# MINI_SAM_D51_r020_b002_Seeed.net
KiCad netlist of a schematic drawn in EAGLE
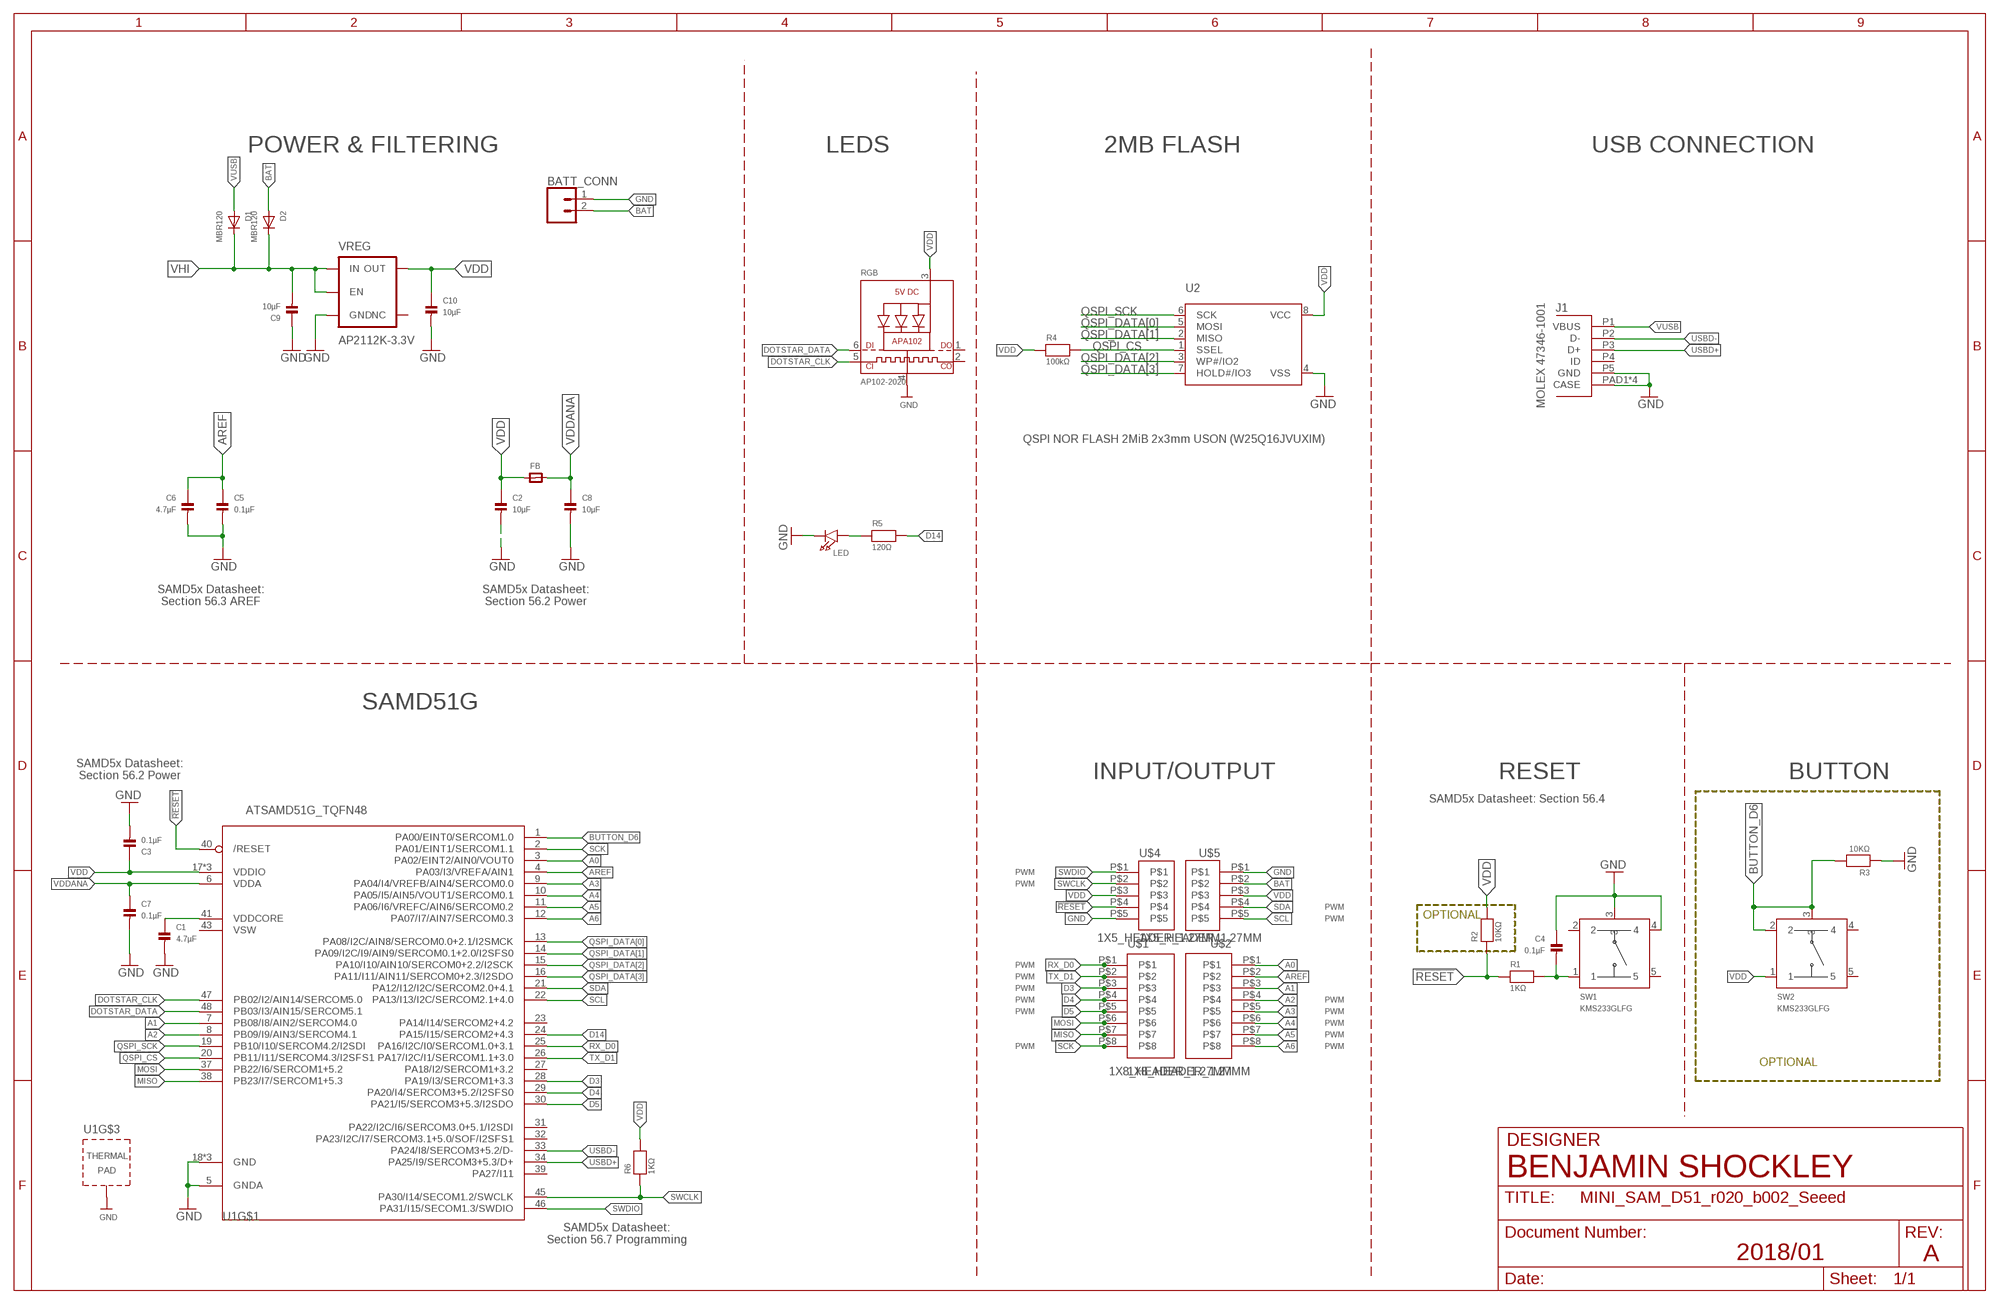
[diagram p0: schematic, sheet 1]

(export (version "E")
  (design (tool "Eeschema 10.0.6"))
  (components
    (comp (ref "BATT_CONN")
      (value "CONN_02-JST-2MM-SMT")
      (footprint "eagle-import:JST-2-SMD")
      (libsource (lib "eagle-import") (part "CONN_02-JST-2MM-SMT"))
    )
    (comp (ref "C1")
      (value "4.7µF")
      (footprint "eagle-import:_0603MP")
      (libsource (lib "eagle-import") (part "CAP_CERAMIC_0603MP"))
    )
    (comp (ref "C2")
      (value "10µF")
      (footprint "eagle-import:_0603MP")
      (libsource (lib "eagle-import") (part "CAP_CERAMIC_0603MP"))
    )
    (comp (ref "C3")
      (value "0.1µF")
      (footprint "eagle-import:_0603MP")
      (libsource (lib "eagle-import") (part "CAP_CERAMIC_0603MP"))
    )
    (comp (ref "C4")
      (value "0.1µF")
      (footprint "eagle-import:_0603MP")
      (libsource (lib "eagle-import") (part "CAP_CERAMIC_0603MP"))
    )
    (comp (ref "C5")
      (value "0.1µF")
      (footprint "eagle-import:_0603MP")
      (libsource (lib "eagle-import") (part "CAP_CERAMIC_0603MP"))
    )
    (comp (ref "C6")
      (value "4.7µF")
      (footprint "eagle-import:_0603MP")
      (libsource (lib "eagle-import") (part "CAP_CERAMIC_0603MP"))
    )
    (comp (ref "C7")
      (value "0.1µF")
      (footprint "eagle-import:_0603MP")
      (libsource (lib "eagle-import") (part "CAP_CERAMIC_0603MP"))
    )
    (comp (ref "C8")
      (value "10µF")
      (footprint "eagle-import:_0603MP")
      (libsource (lib "eagle-import") (part "CAP_CERAMIC_0603MP"))
    )
    (comp (ref "C9")
      (value "10µF")
      (footprint "eagle-import:_0603MP")
      (libsource (lib "eagle-import") (part "CAP_CERAMIC_0603MP"))
    )
    (comp (ref "C10")
      (value "10µF")
      (footprint "eagle-import:_0603MP")
      (libsource (lib "eagle-import") (part "CAP_CERAMIC_0603MP"))
    )
    (comp (ref "D1")
      (value "MBR120")
      (footprint "eagle-import:SOD-123FL")
      (libsource (lib "eagle-import") (part "DIODE_SOD-123FL"))
    )
    (comp (ref "D2")
      (value "MBR120")
      (footprint "eagle-import:SOD-123FL")
      (libsource (lib "eagle-import") (part "DIODE_SOD-123FL"))
    )
    (comp (ref "FB")
      (value "Impedence: 50 ohm @ 20 MHz, 220 Ohm @ 100 MHz; low DC resistance")
      (footprint "eagle-import:_0603MP")
      (libsource (lib "eagle-import") (part "FERRITE_0603MP"))
    )
    (comp (ref "J1")
      (value "MOLEX_47346-100147346")
      (footprint "eagle-import:MOLEX_47346-1001")
      (libsource (lib "eagle-import") (part "MOLEX_47346-100147346"))
    )
    (comp (ref "LED")
      (value "VLRK31Q1R2-GS08")
      (footprint "eagle-import:REVERSE_MOUNT_LED")
      (libsource (lib "eagle-import") (part "REVERSEMOUNTLED"))
    )
    (comp (ref "R1")
      (value "1KΩ")
      (footprint "eagle-import:_0603MP")
      (libsource (lib "eagle-import") (part "RESISTOR_0603MP"))
    )
    (comp (ref "R2")
      (value "10KΩ")
      (footprint "eagle-import:_0603MP")
      (libsource (lib "eagle-import") (part "RESISTOR_0603MP"))
    )
    (comp (ref "R3")
      (value "10KΩ")
      (footprint "eagle-import:_0603MP")
      (libsource (lib "eagle-import") (part "RESISTOR_0603MP"))
    )
    (comp (ref "R4")
      (value "100kΩ")
      (footprint "eagle-import:_0603MP")
      (libsource (lib "eagle-import") (part "RESISTOR_0603MP"))
    )
    (comp (ref "R5")
      (value "120Ω")
      (footprint "eagle-import:_0603MP")
      (libsource (lib "eagle-import") (part "RESISTOR_0603MP"))
    )
    (comp (ref "R6")
      (value "1KΩ")
      (footprint "eagle-import:_0603MP")
      (libsource (lib "eagle-import") (part "RESISTOR_0603MP"))
    )
    (comp (ref "RGB")
      (value "AP102-2020")
      (footprint "eagle-import:APA102_2020")
      (libsource (lib "eagle-import") (part "APA1022020"))
    )
    (comp (ref "SW1")
      (value "KMS233GLFG")
      (footprint "eagle-import:KMS_SWITCH")
      (libsource (lib "eagle-import") (part "KMS_SWITCHKMS"))
    )
    (comp (ref "SW2")
      (value "KMS233GLFG")
      (footprint "eagle-import:KMS_SWITCH")
      (libsource (lib "eagle-import") (part "KMS_SWITCHKMS"))
    )
    (comp (ref "U$1")
      (value "1X8_HEADER_1.27MM")
      (footprint "eagle-import:1X8_HEADER_1.27MM")
      (libsource (lib "eagle-import") (part "1X8_HEADER_1.27MM"))
    )
    (comp (ref "U$2")
      (value "1X8_HEADER_1.27MM")
      (footprint "eagle-import:1X8_HEADER_1.27MM")
      (libsource (lib "eagle-import") (part "1X8_HEADER_1.27MM"))
    )
    (comp (ref "U$4")
      (value "1X5_HEADER_1.27MM")
      (footprint "eagle-import:1X5_HEADER_1.27MM")
      (libsource (lib "eagle-import") (part "1X5_HEADER_1.27MM"))
    )
    (comp (ref "U$5")
      (value "1X5_HEADER_1.27MM")
      (footprint "eagle-import:1X5_HEADER_1.27MM")
      (libsource (lib "eagle-import") (part "1X5_HEADER_1.27MM"))
    )
    (comp (ref "U1")
      (value "ATSAMD51G_TQFN48")
      (footprint "eagle-import:TQFN48_7MM")
      (libsource (lib "eagle-import") (part "ATSAMD51G_TQFN48"))
    )
    (comp (ref "U2")
      (value "QSPI NOR FLASH 2MiB 2x3mm USON (W25Q16JVUXIM)")
      (footprint "eagle-import:USON8")
      (libsource (lib "eagle-import") (part "SPIFLASH_8PINUX"))
    )
    (comp (ref "VREG")
      (value "AP2112K-3.3V")
      (footprint "eagle-import:SOT23-5")
      (libsource (lib "eagle-import") (part "V_REG_AP2112K-3.3V"))
    )
  )
  (nets
    (net (code "1") (name "/VSW") (class "Default")
      (node (ref "U1") (pin "43") (pinfunction "VSW_43") (pintype "power_in"))
    )
    (net (code "2") (name "/~{RESET}") (class "Default")
      (node (ref "R1") (pin "1") (pinfunction "1_1") (pintype "passive"))
      (node (ref "R2") (pin "1") (pinfunction "1_1") (pintype "passive"))
      (node (ref "U$4") (pin "P$4") (pinfunction "P$4_P$4") (pintype "bidirectional"))
      (node (ref "U1") (pin "40") (pinfunction "/RESET_40") (pintype "bidirectional"))
    )
    (net (code "3") (name "A0") (class "Default")
      (node (ref "U$2") (pin "P$1") (pinfunction "P$1_P$1") (pintype "bidirectional"))
      (node (ref "U1") (pin "3") (pinfunction "PA02/EINT2/AIN0/VOUT0_3") (pintype "bidirectional"))
    )
    (net (code "4") (name "A1") (class "Default")
      (node (ref "U$2") (pin "P$3") (pinfunction "P$3_P$3") (pintype "bidirectional"))
      (node (ref "U1") (pin "7") (pinfunction "PB08/I8/AIN2/SERCOM4.0_7") (pintype "bidirectional"))
    )
    (net (code "5") (name "A2") (class "Default")
      (node (ref "U$2") (pin "P$4") (pinfunction "P$4_P$4") (pintype "bidirectional"))
      (node (ref "U1") (pin "8") (pinfunction "PB09/I9/AIN3/SERCOM4.1_8") (pintype "bidirectional"))
    )
    (net (code "6") (name "A3") (class "Default")
      (node (ref "U$2") (pin "P$5") (pinfunction "P$5_P$5") (pintype "bidirectional"))
      (node (ref "U1") (pin "9") (pinfunction "PA04/I4/VREFB/AIN4/SERCOM0.0_9") (pintype "bidirectional"))
    )
    (net (code "7") (name "A4") (class "Default")
      (node (ref "U$2") (pin "P$6") (pinfunction "P$6_P$6") (pintype "bidirectional"))
      (node (ref "U1") (pin "10") (pinfunction "PA05/I5/AIN5/VOUT1/SERCOM0.1_10") (pintype "bidirectional"))
    )
    (net (code "8") (name "A5") (class "Default")
      (node (ref "U$2") (pin "P$7") (pinfunction "P$7_P$7") (pintype "bidirectional"))
      (node (ref "U1") (pin "11") (pinfunction "PA06/I6/VREFC/AIN6/SERCOM0.2_11") (pintype "bidirectional"))
    )
    (net (code "9") (name "A6") (class "Default")
      (node (ref "U$2") (pin "P$8") (pinfunction "P$8_P$8") (pintype "bidirectional"))
      (node (ref "U1") (pin "12") (pinfunction "PA07/I7/AIN7/SERCOM0.3_12") (pintype "bidirectional"))
    )
    (net (code "10") (name "AREF") (class "Default")
      (node (ref "C5") (pin "1") (pinfunction "P$1_1") (pintype "passive"))
      (node (ref "C6") (pin "1") (pinfunction "P$1_1") (pintype "passive"))
      (node (ref "U$2") (pin "P$2") (pinfunction "P$2_P$2") (pintype "bidirectional"))
      (node (ref "U1") (pin "4") (pinfunction "PA03/I3/VREFA/AIN1_4") (pintype "bidirectional"))
    )
    (net (code "11") (name "BAT") (class "Default")
      (node (ref "BATT_CONN") (pin "2") (pinfunction "1_2") (pintype "passive"))
      (node (ref "D2") (pin "A") (pinfunction "A_A") (pintype "passive"))
      (node (ref "U$5") (pin "P$2") (pinfunction "P$2_P$2") (pintype "bidirectional"))
    )
    (net (code "12") (name "BUTTON_D6") (class "Default")
      (node (ref "R3") (pin "2") (pinfunction "2_2") (pintype "passive"))
      (node (ref "SW2") (pin "2") (pinfunction "2_2") (pintype "bidirectional"))
      (node (ref "SW2") (pin "3") (pinfunction "3_3") (pintype "bidirectional"))
      (node (ref "U1") (pin "1") (pinfunction "PA00/EINT0/SERCOM1.0_1") (pintype "bidirectional"))
    )
    (net (code "13") (name "D3") (class "Default")
      (node (ref "U$1") (pin "P$3") (pinfunction "P$3_P$3") (pintype "bidirectional"))
      (node (ref "U1") (pin "28") (pinfunction "PA19/I3/SERCOM1+3.3_28") (pintype "bidirectional"))
    )
    (net (code "14") (name "D4") (class "Default")
      (node (ref "U$1") (pin "P$4") (pinfunction "P$4_P$4") (pintype "bidirectional"))
      (node (ref "U1") (pin "29") (pinfunction "PA20/I4/SERCOM3+5.2/I2SFS0_29") (pintype "bidirectional"))
    )
    (net (code "15") (name "D5") (class "Default")
      (node (ref "U$1") (pin "P$5") (pinfunction "P$5_P$5") (pintype "bidirectional"))
      (node (ref "U1") (pin "30") (pinfunction "PA21/I5/SERCOM3+5.3/I2SDO_30") (pintype "bidirectional"))
    )
    (net (code "16") (name "D14") (class "Default")
      (node (ref "R5") (pin "2") (pinfunction "2_2") (pintype "passive"))
      (node (ref "U1") (pin "24") (pinfunction "PA15/I15/SERCOM2+4.3_24") (pintype "bidirectional"))
    )
    (net (code "17") (name "DOTSTAR_CLK") (class "Default")
      (node (ref "RGB") (pin "5") (pinfunction "CKI_5") (pintype "input"))
      (node (ref "U1") (pin "47") (pinfunction "PB02/I2/AIN14/SERCOM5.0_47") (pintype "bidirectional"))
    )
    (net (code "18") (name "DOTSTAR_DATA") (class "Default")
      (node (ref "RGB") (pin "6") (pinfunction "DI_6") (pintype "input"))
      (node (ref "U1") (pin "48") (pinfunction "PB03/I3/AIN15/SERCOM5.1_48") (pintype "bidirectional"))
    )
    (net (code "19") (name "GND") (class "Default")
      (node (ref "BATT_CONN") (pin "1") (pinfunction "2_1") (pintype "passive"))
      (node (ref "C1") (pin "2") (pinfunction "P$2_2") (pintype "passive"))
      (node (ref "C10") (pin "2") (pinfunction "P$2_2") (pintype "passive"))
      (node (ref "C2") (pin "2") (pinfunction "P$2_2") (pintype "passive"))
      (node (ref "C3") (pin "2") (pinfunction "P$2_2") (pintype "passive"))
      (node (ref "C4") (pin "1") (pinfunction "P$1_1") (pintype "passive"))
      (node (ref "C5") (pin "2") (pinfunction "P$2_2") (pintype "passive"))
      (node (ref "C6") (pin "2") (pinfunction "P$2_2") (pintype "passive"))
      (node (ref "C7") (pin "2") (pinfunction "P$2_2") (pintype "passive"))
      (node (ref "C8") (pin "2") (pinfunction "P$2_2") (pintype "passive"))
      (node (ref "C9") (pin "1") (pinfunction "P$1_1") (pintype "passive"))
      (node (ref "J1") (pin "P5") (pinfunction "GND_P5") (pintype "power_in"))
      (node (ref "J1") (pin "PAD1") (pinfunction "CASE_PAD1") (pintype "bidirectional"))
      (node (ref "J1") (pin "PAD2") (pinfunction "CASE_PAD2") (pintype "bidirectional"))
      (node (ref "J1") (pin "PAD3") (pinfunction "CASE_PAD3") (pintype "bidirectional"))
      (node (ref "J1") (pin "PAD4") (pinfunction "CASE_PAD4") (pintype "bidirectional"))
      (node (ref "LED") (pin "C") (pinfunction "C_C") (pintype "passive"))
      (node (ref "R3") (pin "1") (pinfunction "1_1") (pintype "passive"))
      (node (ref "RGB") (pin "4") (pinfunction "GND_4") (pintype "power_in"))
      (node (ref "SW1") (pin "3") (pinfunction "3_3") (pintype "bidirectional"))
      (node (ref "SW1") (pin "4") (pinfunction "4_4") (pintype "bidirectional"))
      (node (ref "U$4") (pin "P$5") (pinfunction "P$5_P$5") (pintype "bidirectional"))
      (node (ref "U$5") (pin "P$1") (pinfunction "P$1_P$1") (pintype "bidirectional"))
      (node (ref "U1") (pin "18") (pinfunction "GND_18") (pintype "power_in"))
      (node (ref "U1") (pin "35") (pinfunction "GND_35") (pintype "power_in"))
      (node (ref "U1") (pin "42") (pinfunction "GND_42") (pintype "power_in"))
      (node (ref "U1") (pin "5") (pinfunction "GNDA_5") (pintype "power_in"))
      (node (ref "U1") (pin "THERMAL") (pinfunction "TP_THERMAL") (pintype "power_in"))
      (node (ref "U2") (pin "4") (pinfunction "VSS_4") (pintype "bidirectional"))
      (node (ref "VREG") (pin "2") (pinfunction "GND_2") (pintype "input"))
    )
    (net (code "20") (name "MISO") (class "Default")
      (node (ref "U$1") (pin "P$7") (pinfunction "P$7_P$7") (pintype "bidirectional"))
      (node (ref "U1") (pin "38") (pinfunction "PB23/I7/SERCOM1+5.3_38") (pintype "bidirectional"))
    )
    (net (code "21") (name "MOSI") (class "Default")
      (node (ref "U$1") (pin "P$6") (pinfunction "P$6_P$6") (pintype "bidirectional"))
      (node (ref "U1") (pin "37") (pinfunction "PB22/I6/SERCOM1+5.2_37") (pintype "bidirectional"))
    )
    (net (code "22") (name "Net-(C1-P$1)") (class "Default")
      (node (ref "C1") (pin "1") (pinfunction "P$1_1") (pintype "passive"))
      (node (ref "U1") (pin "41") (pinfunction "VDDCORE_41") (pintype "power_in"))
    )
    (net (code "23") (name "Net-(C4-P$2)") (class "Default")
      (node (ref "C4") (pin "2") (pinfunction "P$2_2") (pintype "passive"))
      (node (ref "R1") (pin "2") (pinfunction "2_2") (pintype "passive"))
      (node (ref "SW1") (pin "1") (pinfunction "1_1") (pintype "bidirectional"))
    )
    (net (code "24") (name "Net-(LED-PadA)") (class "Default")
      (node (ref "LED") (pin "A") (pinfunction "A_A") (pintype "passive"))
      (node (ref "R5") (pin "1") (pinfunction "1_1") (pintype "passive"))
    )
    (net (code "25") (name "QSPI_CS") (class "Default")
      (node (ref "R4") (pin "2") (pinfunction "2_2") (pintype "passive"))
      (node (ref "U1") (pin "20") (pinfunction "PB11/I11/SERCOM4.3/I2SFS1_20") (pintype "bidirectional"))
      (node (ref "U2") (pin "1") (pinfunction "SSEL_1") (pintype "bidirectional"))
    )
    (net (code "26") (name "QSPI_DATA[0]") (class "Default")
      (node (ref "U1") (pin "13") (pinfunction "PA08/I2C/AIN8/SERCOM0.0+2.1/I2SMCK_13") (pintype "bidirectional"))
      (node (ref "U2") (pin "5") (pinfunction "MOSI_5") (pintype "bidirectional"))
    )
    (net (code "27") (name "QSPI_DATA[1]") (class "Default")
      (node (ref "U1") (pin "14") (pinfunction "PA09/I2C/I9/AIN9/SERCOM0.1+2.0/I2SFS0_14") (pintype "bidirectional"))
      (node (ref "U2") (pin "2") (pinfunction "MISO_2") (pintype "bidirectional"))
    )
    (net (code "28") (name "QSPI_DATA[2]") (class "Default")
      (node (ref "U1") (pin "15") (pinfunction "PA10/I10/AIN10/SERCOM0+2.2/I2SCK_15") (pintype "bidirectional"))
      (node (ref "U2") (pin "3") (pinfunction "WP#/IO2_3") (pintype "bidirectional"))
    )
    (net (code "29") (name "QSPI_DATA[3]") (class "Default")
      (node (ref "U1") (pin "16") (pinfunction "PA11/I11/AIN11/SERCOM0+2.3/I2SDO_16") (pintype "bidirectional"))
      (node (ref "U2") (pin "7") (pinfunction "HOLD#/IO3_7") (pintype "bidirectional"))
    )
    (net (code "30") (name "QSPI_SCK") (class "Default")
      (node (ref "U1") (pin "19") (pinfunction "PB10/I10/SERCOM4.2/I2SDI_19") (pintype "bidirectional"))
      (node (ref "U2") (pin "6") (pinfunction "SCK_6") (pintype "bidirectional"))
    )
    (net (code "31") (name "RX_D0") (class "Default")
      (node (ref "U$1") (pin "P$1") (pinfunction "P$1_P$1") (pintype "bidirectional"))
      (node (ref "U1") (pin "25") (pinfunction "PA16/I2C/I0/SERCOM1.0+3.1_25") (pintype "bidirectional"))
    )
    (net (code "32") (name "SCK") (class "Default")
      (node (ref "U$1") (pin "P$8") (pinfunction "P$8_P$8") (pintype "bidirectional"))
      (node (ref "U1") (pin "2") (pinfunction "PA01/EINT1/SERCOM1.1_2") (pintype "bidirectional"))
    )
    (net (code "33") (name "SCL") (class "Default")
      (node (ref "U$5") (pin "P$5") (pinfunction "P$5_P$5") (pintype "bidirectional"))
      (node (ref "U1") (pin "22") (pinfunction "PA13/I13/I2C/SERCOM2.1+4.0_22") (pintype "bidirectional"))
    )
    (net (code "34") (name "SDA") (class "Default")
      (node (ref "U$5") (pin "P$4") (pinfunction "P$4_P$4") (pintype "bidirectional"))
      (node (ref "U1") (pin "21") (pinfunction "PA12/I12/I2C/SERCOM2.0+4.1_21") (pintype "bidirectional"))
    )
    (net (code "35") (name "SWCLK") (class "Default")
      (node (ref "R6") (pin "1") (pinfunction "1_1") (pintype "passive"))
      (node (ref "U$4") (pin "P$2") (pinfunction "P$2_P$2") (pintype "bidirectional"))
      (node (ref "U1") (pin "45") (pinfunction "PA30/I14/SECOM1.2/SWCLK_45") (pintype "bidirectional"))
    )
    (net (code "36") (name "SWDIO") (class "Default")
      (node (ref "U$4") (pin "P$1") (pinfunction "P$1_P$1") (pintype "bidirectional"))
      (node (ref "U1") (pin "46") (pinfunction "PA31/I15/SECOM1.3/SWDIO_46") (pintype "bidirectional"))
    )
    (net (code "37") (name "TX_D1") (class "Default")
      (node (ref "U$1") (pin "P$2") (pinfunction "P$2_P$2") (pintype "bidirectional"))
      (node (ref "U1") (pin "26") (pinfunction "PA17/I2C/I1/SERCOM1.1+3.0_26") (pintype "bidirectional"))
    )
    (net (code "38") (name "USBD+") (class "Default")
      (node (ref "J1") (pin "P3") (pinfunction "D+_P3") (pintype "bidirectional"))
      (node (ref "U1") (pin "34") (pinfunction "PA25/I9/SERCOM3+5.3/D+_34") (pintype "bidirectional"))
    )
    (net (code "39") (name "USBD-") (class "Default")
      (node (ref "J1") (pin "P2") (pinfunction "D-_P2") (pintype "bidirectional"))
      (node (ref "U1") (pin "33") (pinfunction "PA24/I8/SERCOM3+5.2/D-_33") (pintype "bidirectional"))
    )
    (net (code "40") (name "VDD") (class "Default")
      (node (ref "C10") (pin "1") (pinfunction "P$1_1") (pintype "passive"))
      (node (ref "C2") (pin "1") (pinfunction "P$1_1") (pintype "passive"))
      (node (ref "C3") (pin "1") (pinfunction "P$1_1") (pintype "passive"))
      (node (ref "FB") (pin "1") (pinfunction "P$1_1") (pintype "passive"))
      (node (ref "R2") (pin "2") (pinfunction "2_2") (pintype "passive"))
      (node (ref "R4") (pin "1") (pinfunction "1_1") (pintype "passive"))
      (node (ref "R6") (pin "2") (pinfunction "2_2") (pintype "passive"))
      (node (ref "RGB") (pin "3") (pinfunction "VDD_3") (pintype "power_in"))
      (node (ref "SW2") (pin "1") (pinfunction "1_1") (pintype "bidirectional"))
      (node (ref "U$4") (pin "P$3") (pinfunction "P$3_P$3") (pintype "bidirectional"))
      (node (ref "U$5") (pin "P$3") (pinfunction "P$3_P$3") (pintype "bidirectional"))
      (node (ref "U1") (pin "17") (pinfunction "VDDIO_17") (pintype "power_in"))
      (node (ref "U1") (pin "36") (pinfunction "VDDIO_36") (pintype "power_in"))
      (node (ref "U1") (pin "44") (pinfunction "VDDIO_44") (pintype "power_in"))
      (node (ref "U2") (pin "8") (pinfunction "VCC_8") (pintype "bidirectional"))
      (node (ref "VREG") (pin "5") (pinfunction "OUT_5") (pintype "passive"))
    )
    (net (code "41") (name "VDDANA") (class "Default")
      (node (ref "C7") (pin "1") (pinfunction "P$1_1") (pintype "passive"))
      (node (ref "C8") (pin "1") (pinfunction "P$1_1") (pintype "passive"))
      (node (ref "FB") (pin "2") (pinfunction "P$2_2") (pintype "passive"))
      (node (ref "U1") (pin "6") (pinfunction "VDDA_6") (pintype "power_in"))
    )
    (net (code "42") (name "VHI") (class "Default")
      (node (ref "C9") (pin "2") (pinfunction "P$2_2") (pintype "passive"))
      (node (ref "D1") (pin "C") (pinfunction "C_C") (pintype "passive"))
      (node (ref "D2") (pin "C") (pinfunction "C_C") (pintype "passive"))
      (node (ref "VREG") (pin "1") (pinfunction "IN_1") (pintype "input"))
      (node (ref "VREG") (pin "3") (pinfunction "EN_3") (pintype "input"))
    )
    (net (code "43") (name "VUSB") (class "Default")
      (node (ref "D1") (pin "A") (pinfunction "A_A") (pintype "passive"))
      (node (ref "J1") (pin "P1") (pinfunction "VBUS_P1") (pintype "power_in"))
    )
    (net (code "44") (name "unconnected-(J1-ID-PadP4)") (class "Default")
      (node (ref "J1") (pin "P4") (pinfunction "ID_P4") (pintype "bidirectional"))
    )
    (net (code "45") (name "unconnected-(RGB-CKO-Pad2)") (class "Default")
      (node (ref "RGB") (pin "2") (pinfunction "CKO_2") (pintype "output"))
    )
    (net (code "46") (name "unconnected-(RGB-DO-Pad1)") (class "Default")
      (node (ref "RGB") (pin "1") (pinfunction "DO_1") (pintype "output"))
    )
    (net (code "47") (name "unconnected-(SW1-Pad2)") (class "Default")
      (node (ref "SW1") (pin "2") (pinfunction "2_2") (pintype "bidirectional"))
    )
    (net (code "48") (name "unconnected-(SW1-Pad5)") (class "Default")
      (node (ref "SW1") (pin "5") (pinfunction "5_5") (pintype "bidirectional"))
    )
    (net (code "49") (name "unconnected-(SW2-Pad4)") (class "Default")
      (node (ref "SW2") (pin "4") (pinfunction "4_4") (pintype "bidirectional"))
    )
    (net (code "50") (name "unconnected-(SW2-Pad5)") (class "Default")
      (node (ref "SW2") (pin "5") (pinfunction "5_5") (pintype "bidirectional"))
    )
    (net (code "51") (name "unconnected-(U1A-PA14{slash}I14{slash}SERCOM2+4.2-Pad23)") (class "Default")
      (node (ref "U1") (pin "23") (pinfunction "PA14/I14/SERCOM2+4.2_23") (pintype "bidirectional"))
    )
    (net (code "52") (name "unconnected-(U1A-PA18{slash}I2{slash}SERCOM1+3.2-Pad27)") (class "Default")
      (node (ref "U1") (pin "27") (pinfunction "PA18/I2/SERCOM1+3.2_27") (pintype "bidirectional"))
    )
    (net (code "53") (name "unconnected-(U1A-PA22{slash}I2C{slash}I6{slash}SERCOM3.0+5.1{slash}I2SDI-Pad31)") (class "Default")
      (node (ref "U1") (pin "31") (pinfunction "PA22/I2C/I6/SERCOM3.0+5.1/I2SDI_31") (pintype "bidirectional"))
    )
    (net (code "54") (name "unconnected-(U1A-PA23{slash}I2C{slash}I7{slash}SERCOM3.1+5.0{slash}SOF{slash}I2SFS1-Pad32)") (class "Default")
      (node (ref "U1") (pin "32") (pinfunction "PA23/I2C/I7/SERCOM3.1+5.0/SOF/I2SFS1_32") (pintype "bidirectional"))
    )
    (net (code "55") (name "unconnected-(U1A-PA27{slash}I11-Pad39)") (class "Default")
      (node (ref "U1") (pin "39") (pinfunction "PA27/I11_39") (pintype "bidirectional"))
    )
    (net (code "56") (name "unconnected-(VREG-NC-Pad4)") (class "Default")
      (node (ref "VREG") (pin "4") (pinfunction "NC_4") (pintype "input"))
    )
  )
)
